# design.net
KiCad netlist of a schematic drawn in Altium Designer
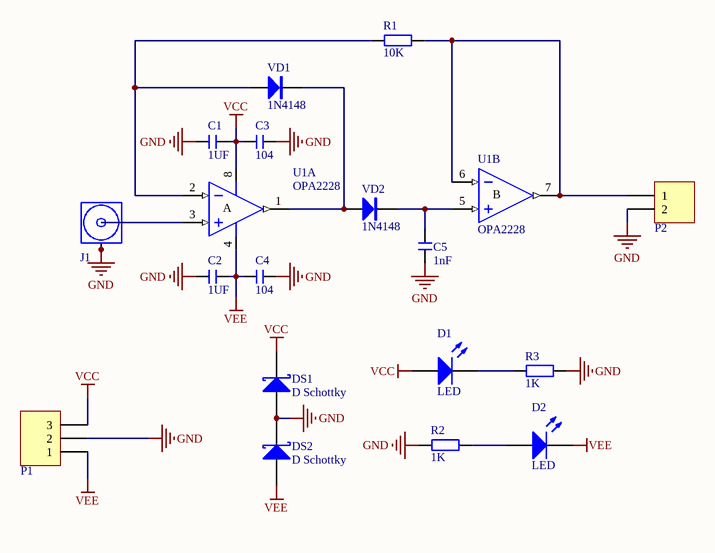
[diagram p0: 峰值检测.SchDoc]

(export (version "E")
  (design (tool "Eeschema 10.0.6"))
  (components
    (comp (ref "C1")
      (value "1UF")
      (footprint "C 0603")
      (description "无极性贴片电容")
      (fields (field (name "版权归属") "源创客"))
      (libsource (lib "电阻-电容-电感") (part "C"))
    )
    (comp (ref "C2")
      (value "1UF")
      (footprint "C 0603")
      (description "无极性贴片电容")
      (fields (field (name "版权归属") "源创客"))
      (libsource (lib "电阻-电容-电感") (part "C"))
    )
    (comp (ref "C3")
      (value "104")
      (footprint "C 0603")
      (description "无极性贴片电容")
      (fields (field (name "版权归属") "源创客"))
      (libsource (lib "电阻-电容-电感") (part "C"))
    )
    (comp (ref "C4")
      (value "104")
      (footprint "C 0603")
      (description "无极性贴片电容")
      (fields (field (name "版权归属") "源创客"))
      (libsource (lib "电阻-电容-电感") (part "C"))
    )
    (comp (ref "C5")
      (value "1nF")
      (footprint "C 0603")
      (description "无极性贴片电容")
      (fields (field (name "版权归属") "源创客"))
      (libsource (lib "电阻-电容-电感") (part "C"))
    )
    (comp (ref "D1")
      (value "LED")
      (footprint "LED_0805")
      (description "发光二极管")
      (fields (field (name "PUBLISHER") "Altium Limited"))
      (libsource (lib "LIB") (part "LED"))
    )
    (comp (ref "D2")
      (value "LED")
      (footprint "LED_0805")
      (description "发光二极管")
      (fields (field (name "PUBLISHER") "Altium Limited"))
      (libsource (lib "LIB") (part "LED"))
    )
    (comp (ref "DS1")
      (value "D Schottky")
      (footprint "DIODE-SMA")
      (description "Schottky Diode")
      (fields (field (name "PUBLISHER") "Altium Limited"))
      (libsource (lib "LIB") (part "D Schottky"))
    )
    (comp (ref "DS2")
      (value "D Schottky")
      (footprint "DIODE-SMA")
      (description "Schottky Diode")
      (fields (field (name "PUBLISHER") "Altium Limited"))
      (libsource (lib "LIB") (part "D Schottky"))
    )
    (comp (ref "J1") (value "COAX") (footprint "MCX5.08-5-H") (libsource (lib "LIB") (part "COAX")))
    (comp (ref "P1")
      (value "Header 3")
      (footprint "HDR3X1_B2")
      (description "接插件")
      (fields (field (name "PUBLISHER") "Altium Limited"))
      (libsource (lib "LIB") (part "Header 3"))
    )
    (comp (ref "P2")
      (value "Header 2")
      (footprint "HDR2X1_B2")
      (description "接插件")
      (fields (field (name "PUBLISHER") "Altium Limited"))
      (libsource (lib "LIB") (part "Header 2"))
    )
    (comp (ref "R1")
      (value "10K")
      (footprint "R 0603")
      (description "贴片电阻")
      (fields (field (name "版权归属") "源创客"))
      (libsource (lib "电阻-电容-电感") (part "R"))
    )
    (comp (ref "R2")
      (value "1K")
      (footprint "R 0805")
      (description "贴片电阻")
      (fields (field (name "版权归属") "源创客"))
      (libsource (lib "电阻-电容-电感") (part "R"))
    )
    (comp (ref "R3")
      (value "1K")
      (footprint "R 0805")
      (description "贴片电阻")
      (fields (field (name "版权归属") "源创客"))
      (libsource (lib "电阻-电容-电感") (part "R"))
    )
    (comp (ref "U1")
      (value "OPA2228")
      (footprint "SOIC8_N")
      (description "高精度低噪声运算放大器")
      (libsource (lib "LIB") (part "OPA2228"))
    )
    (comp (ref "VD1")
      (value "1N4148")
      (footprint "SOD-323")
      (description "高速开关二极管")
      (fields (field (name "版权归属") "源创客"))
      (libsource (lib "二极管-整流桥") (part "1N4148"))
    )
    (comp (ref "VD2")
      (value "1N4148")
      (footprint "SOD-323")
      (description "高速开关二极管")
      (fields (field (name "版权归属") "源创客"))
      (libsource (lib "二极管-整流桥") (part "1N4148"))
    )
  )
  (nets
    (net (code "1") (name "GND") (class "Default")
      (node (ref "C1") (pin "2") (pinfunction "2_2") (pintype "passive"))
      (node (ref "C2") (pin "2") (pinfunction "2_2") (pintype "passive"))
      (node (ref "C3") (pin "1") (pinfunction "1_1") (pintype "passive"))
      (node (ref "C4") (pin "1") (pinfunction "1_1") (pintype "passive"))
      (node (ref "C5") (pin "1") (pinfunction "1_1") (pintype "passive"))
      (node (ref "DS1") (pin "1") (pinfunction "1_1") (pintype "passive"))
      (node (ref "DS2") (pin "2") (pinfunction "2_2") (pintype "passive"))
      (node (ref "J1") (pin "2") (pinfunction "GND_2") (pintype "passive"))
      (node (ref "J1") (pin "3") (pinfunction "GND_3") (pintype "passive"))
      (node (ref "J1") (pin "4") (pinfunction "GND_4") (pintype "passive"))
      (node (ref "J1") (pin "5") (pinfunction "GND_5") (pintype "passive"))
      (node (ref "P1") (pin "2") (pinfunction "2_2") (pintype "passive"))
      (node (ref "P2") (pin "2") (pinfunction "2_2") (pintype "passive"))
      (node (ref "R2") (pin "1") (pinfunction "1_1") (pintype "passive"))
      (node (ref "R3") (pin "2") (pinfunction "2_2") (pintype "passive"))
    )
    (net (code "2") (name "Net-(D1-K)") (class "Default")
      (node (ref "D1") (pin "2") (pinfunction "K_2") (pintype "passive"))
      (node (ref "R3") (pin "1") (pinfunction "1_1") (pintype "passive"))
    )
    (net (code "3") (name "Net-(D2-A)") (class "Default")
      (node (ref "D2") (pin "1") (pinfunction "A_1") (pintype "passive"))
      (node (ref "R2") (pin "2") (pinfunction "2_2") (pintype "passive"))
    )
    (net (code "4") (name "Net-(J1-Signal)") (class "Default")
      (node (ref "J1") (pin "1") (pinfunction "Signal_1") (pintype "passive"))
      (node (ref "U1") (pin "3") (pinfunction "IN+_3") (pintype "input"))
    )
    (net (code "5") (name "Net-(U1A-IN-)") (class "Default")
      (node (ref "R1") (pin "1") (pinfunction "1_1") (pintype "passive"))
      (node (ref "U1") (pin "2") (pinfunction "IN-_2") (pintype "input"))
      (node (ref "VD1") (pin "1") (pinfunction "A_1") (pintype "passive"))
    )
    (net (code "6") (name "Net-(U1A-OUT)") (class "Default")
      (node (ref "U1") (pin "1") (pinfunction "OUT_1") (pintype "output"))
      (node (ref "VD1") (pin "2") (pinfunction "K_2") (pintype "passive"))
      (node (ref "VD2") (pin "1") (pinfunction "A_1") (pintype "passive"))
    )
    (net (code "7") (name "Net-(U1B-IN+)") (class "Default")
      (node (ref "C5") (pin "2") (pinfunction "2_2") (pintype "passive"))
      (node (ref "U1") (pin "5") (pinfunction "IN+_5") (pintype "input"))
      (node (ref "VD2") (pin "2") (pinfunction "K_2") (pintype "passive"))
    )
    (net (code "8") (name "Net-(U1B-IN-)") (class "Default")
      (node (ref "P2") (pin "1") (pinfunction "1_1") (pintype "passive"))
      (node (ref "R1") (pin "2") (pinfunction "2_2") (pintype "passive"))
      (node (ref "U1") (pin "6") (pinfunction "IN-_6") (pintype "input"))
      (node (ref "U1") (pin "7") (pinfunction "OUT_7") (pintype "output"))
    )
    (net (code "9") (name "VCC") (class "Default")
      (node (ref "C1") (pin "1") (pinfunction "1_1") (pintype "passive"))
      (node (ref "C3") (pin "2") (pinfunction "2_2") (pintype "passive"))
      (node (ref "D1") (pin "1") (pinfunction "A_1") (pintype "passive"))
      (node (ref "DS1") (pin "2") (pinfunction "2_2") (pintype "passive"))
      (node (ref "P1") (pin "3") (pinfunction "3_3") (pintype "passive"))
      (node (ref "U1") (pin "8") (pinfunction "V+_8") (pintype "power_in"))
    )
    (net (code "10") (name "VEE") (class "Default")
      (node (ref "C2") (pin "1") (pinfunction "1_1") (pintype "passive"))
      (node (ref "C4") (pin "2") (pinfunction "2_2") (pintype "passive"))
      (node (ref "D2") (pin "2") (pinfunction "K_2") (pintype "passive"))
      (node (ref "DS2") (pin "1") (pinfunction "1_1") (pintype "passive"))
      (node (ref "P1") (pin "1") (pinfunction "1_1") (pintype "passive"))
      (node (ref "U1") (pin "4") (pinfunction "V-_4") (pintype "power_in"))
    )
  )
)
